# Battery_Shield.net
KiCad netlist of a schematic drawn in EAGLE
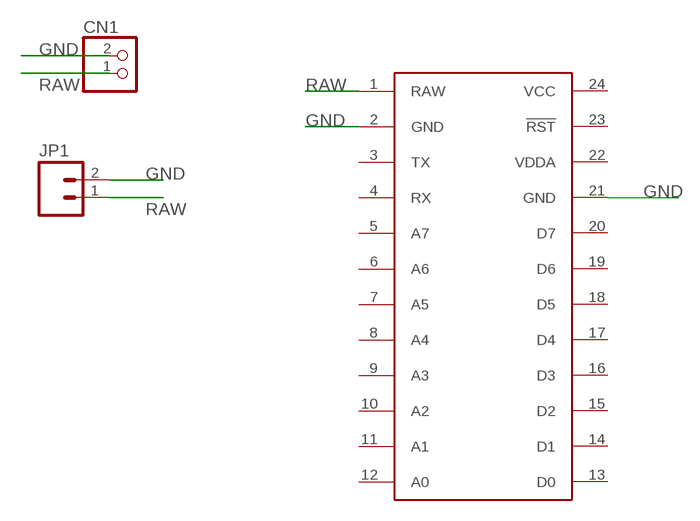
[diagram p0: schematic, sheet 1]

(export (version "E")
  (design (tool "Eeschema 10.0.6"))
  (components
    (comp (ref "CN1")
      (value "JST_2PIN-THM")
      (footprint "eagle-import:JST-PH-2-THM")
      (libsource (lib "eagle-import") (part "JST_2PIN-THM"))
    )
    (comp (ref "JP1")
      (value "M02PTH4")
      (footprint "eagle-import:1X02_XTRA_BIG")
      (libsource (lib "eagle-import") (part "M02PTH4"))
    )
    (comp (ref "U$1")
      (value "SPARK_CORECORE")
      (footprint "eagle-import:SPARK_CORE")
      (libsource (lib "eagle-import") (part "SPARK_CORECORE"))
    )
  )
  (nets
    (net (code "1") (name "/GND") (class "Default")
      (node (ref "CN1") (pin "2") (pinfunction "1_2") (pintype "passive"))
      (node (ref "JP1") (pin "2") (pinfunction "2_2") (pintype "passive"))
      (node (ref "U$1") (pin "2") (pinfunction "GND_2") (pintype "power_in"))
      (node (ref "U$1") (pin "21") (pinfunction "GND_21") (pintype "power_in"))
    )
    (net (code "2") (name "/RAW") (class "Default")
      (node (ref "CN1") (pin "1") (pinfunction "2_1") (pintype "passive"))
      (node (ref "JP1") (pin "1") (pinfunction "1_1") (pintype "passive"))
      (node (ref "U$1") (pin "1") (pinfunction "RAW_1") (pintype "power_in"))
    )
    (net (code "3") (name "/VCC") (class "Default")
      (node (ref "U$1") (pin "24") (pinfunction "VCC_24") (pintype "power_in"))
    )
    (net (code "4") (name "/VDDA") (class "Default")
      (node (ref "U$1") (pin "22") (pinfunction "VDDA_22") (pintype "power_in"))
    )
    (net (code "5") (name "unconnected-(U$1-A0-Pad12)") (class "Default")
      (node (ref "U$1") (pin "12") (pinfunction "A0_12") (pintype "bidirectional"))
    )
    (net (code "6") (name "unconnected-(U$1-A1-Pad11)") (class "Default")
      (node (ref "U$1") (pin "11") (pinfunction "A1_11") (pintype "bidirectional"))
    )
    (net (code "7") (name "unconnected-(U$1-A2-Pad10)") (class "Default")
      (node (ref "U$1") (pin "10") (pinfunction "A2_10") (pintype "bidirectional"))
    )
    (net (code "8") (name "unconnected-(U$1-A3-Pad9)") (class "Default")
      (node (ref "U$1") (pin "9") (pinfunction "A3_9") (pintype "bidirectional"))
    )
    (net (code "9") (name "unconnected-(U$1-A4-Pad8)") (class "Default")
      (node (ref "U$1") (pin "8") (pinfunction "A4_8") (pintype "bidirectional"))
    )
    (net (code "10") (name "unconnected-(U$1-A5-Pad7)") (class "Default")
      (node (ref "U$1") (pin "7") (pinfunction "A5_7") (pintype "bidirectional"))
    )
    (net (code "11") (name "unconnected-(U$1-A6-Pad6)") (class "Default")
      (node (ref "U$1") (pin "6") (pinfunction "A6_6") (pintype "bidirectional"))
    )
    (net (code "12") (name "unconnected-(U$1-A7-Pad5)") (class "Default")
      (node (ref "U$1") (pin "5") (pinfunction "A7_5") (pintype "bidirectional"))
    )
    (net (code "13") (name "unconnected-(U$1-D0-Pad13)") (class "Default")
      (node (ref "U$1") (pin "13") (pinfunction "D0_13") (pintype "bidirectional"))
    )
    (net (code "14") (name "unconnected-(U$1-D1-Pad14)") (class "Default")
      (node (ref "U$1") (pin "14") (pinfunction "D1_14") (pintype "bidirectional"))
    )
    (net (code "15") (name "unconnected-(U$1-D2-Pad15)") (class "Default")
      (node (ref "U$1") (pin "15") (pinfunction "D2_15") (pintype "bidirectional"))
    )
    (net (code "16") (name "unconnected-(U$1-D3-Pad16)") (class "Default")
      (node (ref "U$1") (pin "16") (pinfunction "D3_16") (pintype "bidirectional"))
    )
    (net (code "17") (name "unconnected-(U$1-D4-Pad17)") (class "Default")
      (node (ref "U$1") (pin "17") (pinfunction "D4_17") (pintype "bidirectional"))
    )
    (net (code "18") (name "unconnected-(U$1-D5-Pad18)") (class "Default")
      (node (ref "U$1") (pin "18") (pinfunction "D5_18") (pintype "bidirectional"))
    )
    (net (code "19") (name "unconnected-(U$1-D6-Pad19)") (class "Default")
      (node (ref "U$1") (pin "19") (pinfunction "D6_19") (pintype "bidirectional"))
    )
    (net (code "20") (name "unconnected-(U$1-D7-Pad20)") (class "Default")
      (node (ref "U$1") (pin "20") (pinfunction "D7_20") (pintype "bidirectional"))
    )
    (net (code "21") (name "unconnected-(U$1-RX-Pad4)") (class "Default")
      (node (ref "U$1") (pin "4") (pinfunction "RX_4") (pintype "bidirectional"))
    )
    (net (code "22") (name "unconnected-(U$1-TX-Pad3)") (class "Default")
      (node (ref "U$1") (pin "3") (pinfunction "TX_3") (pintype "bidirectional"))
    )
    (net (code "23") (name "unconnected-(U$1-~{RST}-Pad23)") (class "Default")
      (node (ref "U$1") (pin "23") (pinfunction "~{RST}_23") (pintype "bidirectional"))
    )
  )
)
